# efuse.net
KiCad netlist of a schematic drawn in Altium Designer
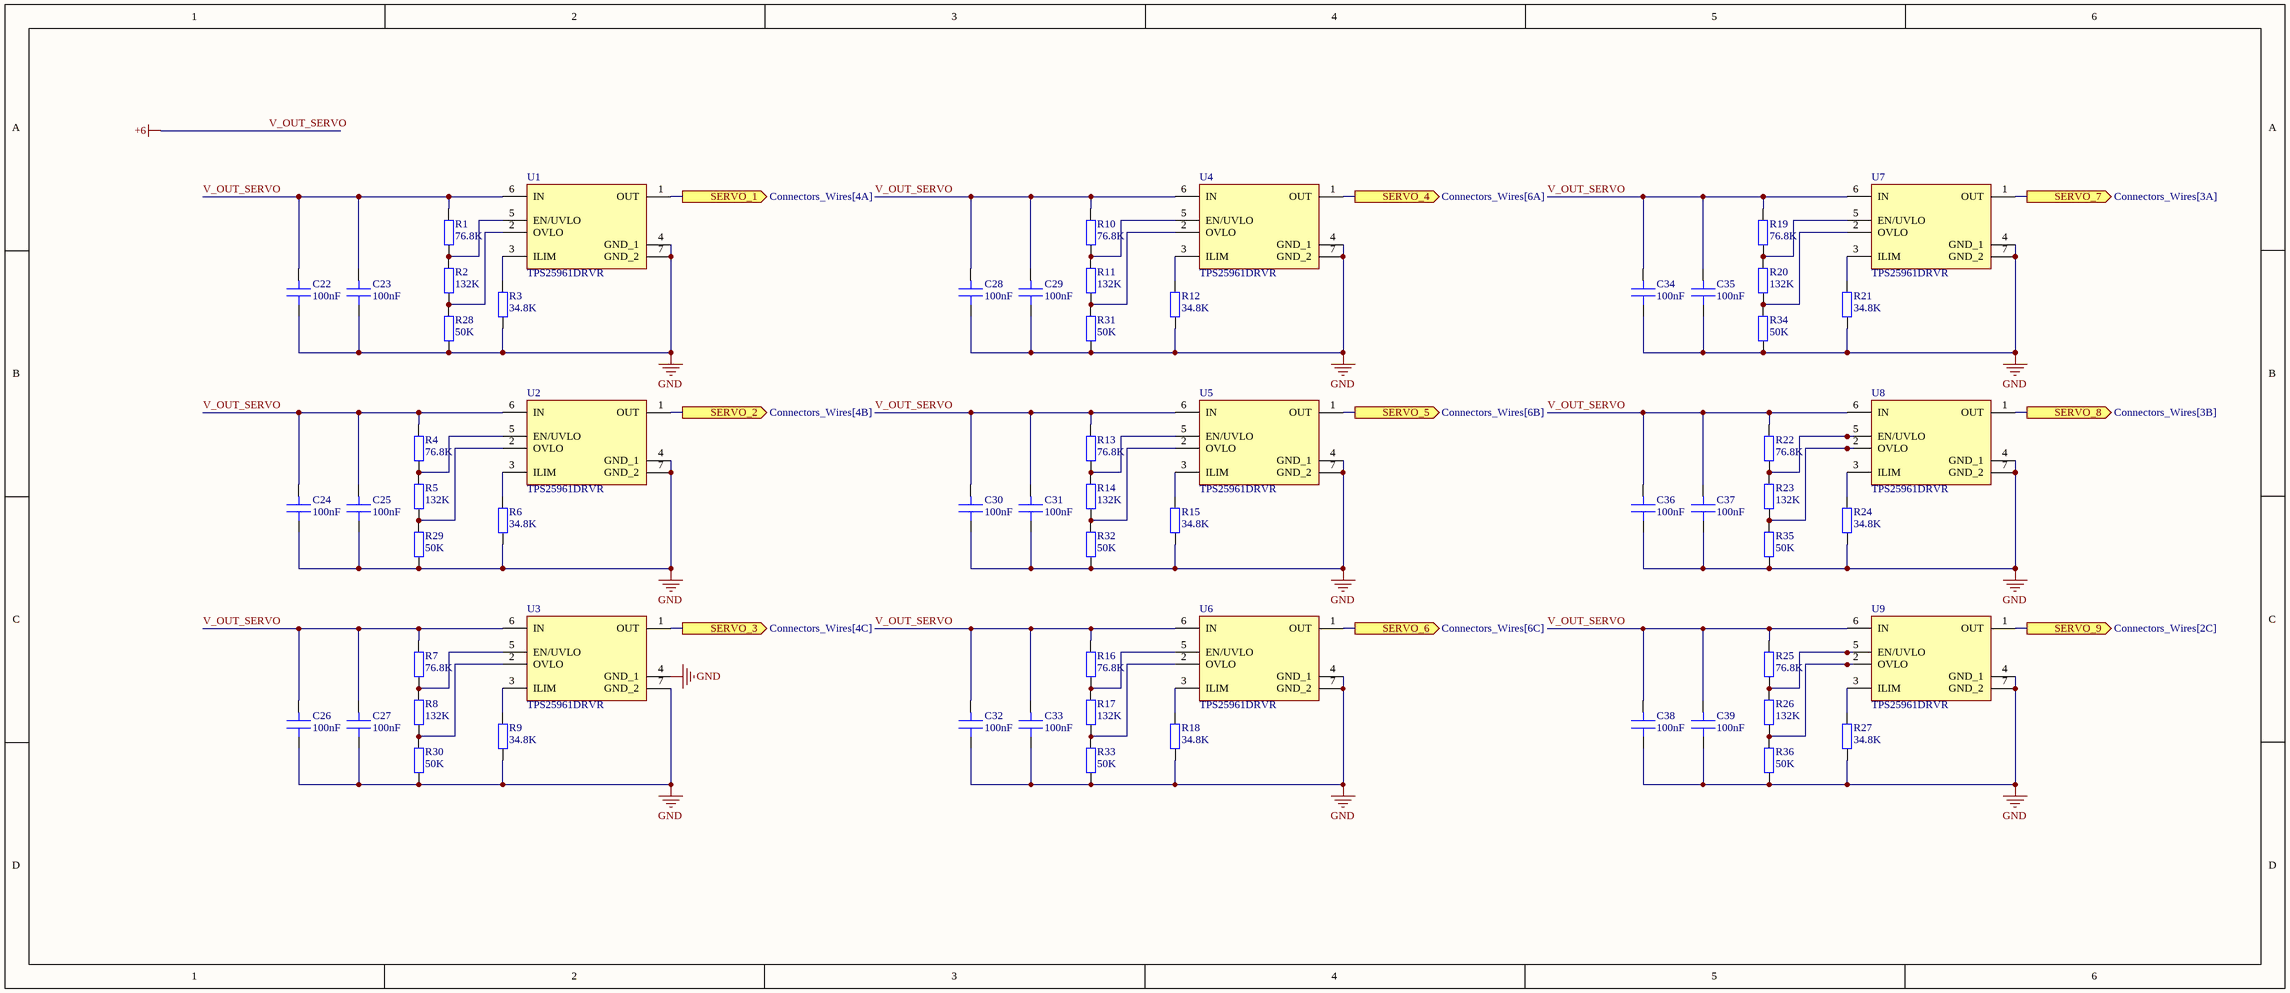
[diagram p0: efuse.SchDoc]

(export (version "E")
  (design (tool "Eeschema 10.0.6"))
  (components
    (comp (ref "C22")
      (value "100nF")
      (footprint "IPC C C0402 NO SILK")
      (description "Input capacitor")
      (libsource (lib "University of British Columbia") (part "Generic CAP 1210"))
    )
    (comp (ref "C23")
      (value "100nF")
      (footprint "IPC C C0402 NO SILK")
      (description "Input capacitor")
      (libsource (lib "University of British Columbia") (part "Generic CAP 1210"))
    )
    (comp (ref "C24")
      (value "100nF")
      (footprint "IPC C C0402 NO SILK")
      (description "Input capacitor")
      (libsource (lib "University of British Columbia") (part "Generic CAP 1210"))
    )
    (comp (ref "C25")
      (value "100nF")
      (footprint "IPC C C0402 NO SILK")
      (description "Input capacitor")
      (libsource (lib "University of British Columbia") (part "Generic CAP 1210"))
    )
    (comp (ref "C26")
      (value "100nF")
      (footprint "IPC C C0402 NO SILK")
      (description "Input capacitor")
      (libsource (lib "University of British Columbia") (part "Generic CAP 1210"))
    )
    (comp (ref "C27")
      (value "100nF")
      (footprint "IPC C C0402 NO SILK")
      (description "Input capacitor")
      (libsource (lib "University of British Columbia") (part "Generic CAP 1210"))
    )
    (comp (ref "C28")
      (value "100nF")
      (footprint "IPC C C0402 NO SILK")
      (description "Input capacitor")
      (libsource (lib "University of British Columbia") (part "Generic CAP 1210"))
    )
    (comp (ref "C29")
      (value "100nF")
      (footprint "IPC C C0402 NO SILK")
      (description "Input capacitor")
      (libsource (lib "University of British Columbia") (part "Generic CAP 1210"))
    )
    (comp (ref "C30")
      (value "100nF")
      (footprint "IPC C C0402 NO SILK")
      (description "Input capacitor")
      (libsource (lib "University of British Columbia") (part "Generic CAP 1210"))
    )
    (comp (ref "C31")
      (value "100nF")
      (footprint "IPC C C0402 NO SILK")
      (description "Input capacitor")
      (libsource (lib "University of British Columbia") (part "Generic CAP 1210"))
    )
    (comp (ref "C32")
      (value "100nF")
      (footprint "IPC C C0402 NO SILK")
      (description "Input capacitor")
      (libsource (lib "University of British Columbia") (part "Generic CAP 1210"))
    )
    (comp (ref "C33")
      (value "100nF")
      (footprint "IPC C C0402 NO SILK")
      (description "Input capacitor")
      (libsource (lib "University of British Columbia") (part "Generic CAP 1210"))
    )
    (comp (ref "C34")
      (value "100nF")
      (footprint "IPC C C0402 NO SILK")
      (description "Input capacitor")
      (libsource (lib "University of British Columbia") (part "Generic CAP 1210"))
    )
    (comp (ref "C35")
      (value "100nF")
      (footprint "IPC C C0402 NO SILK")
      (description "Input capacitor")
      (libsource (lib "University of British Columbia") (part "Generic CAP 1210"))
    )
    (comp (ref "C36")
      (value "100nF")
      (footprint "IPC C C0402 NO SILK")
      (description "Input capacitor")
      (libsource (lib "University of British Columbia") (part "Generic CAP 1210"))
    )
    (comp (ref "C37")
      (value "100nF")
      (footprint "IPC C C0402 NO SILK")
      (description "Input capacitor")
      (libsource (lib "University of British Columbia") (part "Generic CAP 1210"))
    )
    (comp (ref "C38")
      (value "100nF")
      (footprint "IPC C C0402 NO SILK")
      (description "Input capacitor")
      (libsource (lib "University of British Columbia") (part "Generic CAP 1210"))
    )
    (comp (ref "C39")
      (value "100nF")
      (footprint "IPC C C0402 NO SILK")
      (description "Input capacitor")
      (libsource (lib "University of British Columbia") (part "Generic CAP 1210"))
    )
    (comp (ref "R1")
      (value "76.8K")
      (footprint "IPC C R0402 NO SILK")
      (description "Generic RES 0402")
      (libsource (lib "University of British Columbia") (part "Generic RES 0603"))
    )
    (comp (ref "R2")
      (value "132K")
      (footprint "IPC C R0402 NO SILK")
      (description "Generic RES 0402")
      (libsource (lib "University of British Columbia") (part "Generic RES 0603"))
    )
    (comp (ref "R3")
      (value "34.8K")
      (footprint "IPC C R0402 NO SILK")
      (description "Generic RES 0402")
      (libsource (lib "University of British Columbia") (part "Generic RES 0603"))
    )
    (comp (ref "R4")
      (value "76.8K")
      (footprint "IPC C R0402 NO SILK")
      (description "Generic RES 0402")
      (libsource (lib "University of British Columbia") (part "Generic RES 0603"))
    )
    (comp (ref "R5")
      (value "132K")
      (footprint "IPC C R0402 NO SILK")
      (description "Generic RES 0402")
      (libsource (lib "University of British Columbia") (part "Generic RES 0603"))
    )
    (comp (ref "R6")
      (value "34.8K")
      (footprint "IPC C R0402 NO SILK")
      (description "Generic RES 0402")
      (libsource (lib "University of British Columbia") (part "Generic RES 0603"))
    )
    (comp (ref "R7")
      (value "76.8K")
      (footprint "IPC C R0402 NO SILK")
      (description "Generic RES 0402")
      (libsource (lib "University of British Columbia") (part "Generic RES 0603"))
    )
    (comp (ref "R8")
      (value "132K")
      (footprint "IPC C R0402 NO SILK")
      (description "Generic RES 0402")
      (libsource (lib "University of British Columbia") (part "Generic RES 0603"))
    )
    (comp (ref "R9")
      (value "34.8K")
      (footprint "IPC C R0402 NO SILK")
      (description "Generic RES 0402")
      (libsource (lib "University of British Columbia") (part "Generic RES 0603"))
    )
    (comp (ref "R10")
      (value "76.8K")
      (footprint "IPC C R0402 NO SILK")
      (description "Generic RES 0402")
      (libsource (lib "University of British Columbia") (part "Generic RES 0603"))
    )
    (comp (ref "R11")
      (value "132K")
      (footprint "IPC C R0402 NO SILK")
      (description "Generic RES 0402")
      (libsource (lib "University of British Columbia") (part "Generic RES 0603"))
    )
    (comp (ref "R12")
      (value "34.8K")
      (footprint "IPC C R0402 NO SILK")
      (description "Generic RES 0402")
      (libsource (lib "University of British Columbia") (part "Generic RES 0603"))
    )
    (comp (ref "R13")
      (value "76.8K")
      (footprint "IPC C R0402 NO SILK")
      (description "Generic RES 0402")
      (libsource (lib "University of British Columbia") (part "Generic RES 0603"))
    )
    (comp (ref "R14")
      (value "132K")
      (footprint "IPC C R0402 NO SILK")
      (description "Generic RES 0402")
      (libsource (lib "University of British Columbia") (part "Generic RES 0603"))
    )
    (comp (ref "R15")
      (value "34.8K")
      (footprint "IPC C R0402 NO SILK")
      (description "Generic RES 0402")
      (libsource (lib "University of British Columbia") (part "Generic RES 0603"))
    )
    (comp (ref "R16")
      (value "76.8K")
      (footprint "IPC C R0402 NO SILK")
      (description "Generic RES 0402")
      (libsource (lib "University of British Columbia") (part "Generic RES 0603"))
    )
    (comp (ref "R17")
      (value "132K")
      (footprint "IPC C R0402 NO SILK")
      (description "Generic RES 0402")
      (libsource (lib "University of British Columbia") (part "Generic RES 0603"))
    )
    (comp (ref "R18")
      (value "34.8K")
      (footprint "IPC C R0402 NO SILK")
      (description "Generic RES 0402")
      (libsource (lib "University of British Columbia") (part "Generic RES 0603"))
    )
    (comp (ref "R19")
      (value "76.8K")
      (footprint "IPC C R0402 NO SILK")
      (description "Generic RES 0402")
      (libsource (lib "University of British Columbia") (part "Generic RES 0603"))
    )
    (comp (ref "R20")
      (value "132K")
      (footprint "IPC C R0402 NO SILK")
      (description "Generic RES 0402")
      (libsource (lib "University of British Columbia") (part "Generic RES 0603"))
    )
    (comp (ref "R21")
      (value "34.8K")
      (footprint "IPC C R0402 NO SILK")
      (description "Generic RES 0402")
      (libsource (lib "University of British Columbia") (part "Generic RES 0603"))
    )
    (comp (ref "R22")
      (value "76.8K")
      (footprint "IPC C R0402 NO SILK")
      (description "Generic RES 0402")
      (libsource (lib "University of British Columbia") (part "Generic RES 0603"))
    )
    (comp (ref "R23")
      (value "132K")
      (footprint "IPC C R0402 NO SILK")
      (description "Generic RES 0402")
      (libsource (lib "University of British Columbia") (part "Generic RES 0603"))
    )
    (comp (ref "R24")
      (value "34.8K")
      (footprint "IPC C R0402 NO SILK")
      (description "Generic RES 0402")
      (libsource (lib "University of British Columbia") (part "Generic RES 0603"))
    )
    (comp (ref "R25")
      (value "76.8K")
      (footprint "IPC C R0402 NO SILK")
      (description "Generic RES 0402")
      (libsource (lib "University of British Columbia") (part "Generic RES 0603"))
    )
    (comp (ref "R26")
      (value "132K")
      (footprint "IPC C R0402 NO SILK")
      (description "Generic RES 0402")
      (libsource (lib "University of British Columbia") (part "Generic RES 0603"))
    )
    (comp (ref "R27")
      (value "34.8K")
      (footprint "IPC C R0402 NO SILK")
      (description "Generic RES 0402")
      (libsource (lib "University of British Columbia") (part "Generic RES 0603"))
    )
    (comp (ref "R28")
      (value "50K")
      (footprint "IPC C R0402 NO SILK")
      (description "Generic RES 0402")
      (libsource (lib "University of British Columbia") (part "Generic RES 0603"))
    )
    (comp (ref "R29")
      (value "50K")
      (footprint "IPC C R0402 NO SILK")
      (description "Generic RES 0402")
      (libsource (lib "University of British Columbia") (part "Generic RES 0603"))
    )
    (comp (ref "R30")
      (value "50K")
      (footprint "IPC C R0402 NO SILK")
      (description "Generic RES 0402")
      (libsource (lib "University of British Columbia") (part "Generic RES 0603"))
    )
    (comp (ref "R31")
      (value "50K")
      (footprint "IPC C R0402 NO SILK")
      (description "Generic RES 0402")
      (libsource (lib "University of British Columbia") (part "Generic RES 0603"))
    )
    (comp (ref "R32")
      (value "50K")
      (footprint "IPC C R0402 NO SILK")
      (description "Generic RES 0402")
      (libsource (lib "University of British Columbia") (part "Generic RES 0603"))
    )
    (comp (ref "R33")
      (value "50K")
      (footprint "IPC C R0402 NO SILK")
      (description "Generic RES 0402")
      (libsource (lib "University of British Columbia") (part "Generic RES 0603"))
    )
    (comp (ref "R34")
      (value "50K")
      (footprint "IPC C R0402 NO SILK")
      (description "Generic RES 0402")
      (libsource (lib "University of British Columbia") (part "Generic RES 0603"))
    )
    (comp (ref "R35")
      (value "50K")
      (footprint "IPC C R0402 NO SILK")
      (description "Generic RES 0402")
      (libsource (lib "University of British Columbia") (part "Generic RES 0603"))
    )
    (comp (ref "R36")
      (value "50K")
      (footprint "IPC C R0402 NO SILK")
      (description "Generic RES 0402")
      (libsource (lib "University of British Columbia") (part "Generic RES 0603"))
    )
    (comp (ref "U1")
      (value "TPS25961DRVR")
      (footprint "TPS25961DRVR-Footprint-1")
      (description "2.7-V TO 19-V 100-M EFUSE WITH O Hot Swap Controller 1 Channel General Purpose 6-WSON (2x2)")
      (libsource (lib "University of British Columbia") (part "TPS25961DRVR-Symbol-1"))
    )
    (comp (ref "U2")
      (value "TPS25961DRVR")
      (footprint "TPS25961DRVR-Footprint-1")
      (description "2.7-V TO 19-V 100-M EFUSE WITH O Hot Swap Controller 1 Channel General Purpose 6-WSON (2x2)")
      (libsource (lib "University of British Columbia") (part "TPS25961DRVR-Symbol-1"))
    )
    (comp (ref "U3")
      (value "TPS25961DRVR")
      (footprint "TPS25961DRVR-Footprint-1")
      (description "2.7-V TO 19-V 100-M EFUSE WITH O Hot Swap Controller 1 Channel General Purpose 6-WSON (2x2)")
      (libsource (lib "University of British Columbia") (part "TPS25961DRVR-Symbol-1"))
    )
    (comp (ref "U4")
      (value "TPS25961DRVR")
      (footprint "TPS25961DRVR-Footprint-1")
      (description "2.7-V TO 19-V 100-M EFUSE WITH O Hot Swap Controller 1 Channel General Purpose 6-WSON (2x2)")
      (libsource (lib "University of British Columbia") (part "TPS25961DRVR-Symbol-1"))
    )
    (comp (ref "U5")
      (value "TPS25961DRVR")
      (footprint "TPS25961DRVR-Footprint-1")
      (description "2.7-V TO 19-V 100-M EFUSE WITH O Hot Swap Controller 1 Channel General Purpose 6-WSON (2x2)")
      (libsource (lib "University of British Columbia") (part "TPS25961DRVR-Symbol-1"))
    )
    (comp (ref "U6")
      (value "TPS25961DRVR")
      (footprint "TPS25961DRVR-Footprint-1")
      (description "2.7-V TO 19-V 100-M EFUSE WITH O Hot Swap Controller 1 Channel General Purpose 6-WSON (2x2)")
      (libsource (lib "University of British Columbia") (part "TPS25961DRVR-Symbol-1"))
    )
    (comp (ref "U7")
      (value "TPS25961DRVR")
      (footprint "TPS25961DRVR-Footprint-1")
      (description "2.7-V TO 19-V 100-M EFUSE WITH O Hot Swap Controller 1 Channel General Purpose 6-WSON (2x2)")
      (libsource (lib "University of British Columbia") (part "TPS25961DRVR-Symbol-1"))
    )
    (comp (ref "U8")
      (value "TPS25961DRVR")
      (footprint "TPS25961DRVR-Footprint-1")
      (description "2.7-V TO 19-V 100-M EFUSE WITH O Hot Swap Controller 1 Channel General Purpose 6-WSON (2x2)")
      (libsource (lib "University of British Columbia") (part "TPS25961DRVR-Symbol-1"))
    )
    (comp (ref "U9")
      (value "TPS25961DRVR")
      (footprint "TPS25961DRVR-Footprint-1")
      (description "2.7-V TO 19-V 100-M EFUSE WITH O Hot Swap Controller 1 Channel General Purpose 6-WSON (2x2)")
      (libsource (lib "University of British Columbia") (part "TPS25961DRVR-Symbol-1"))
    )
  )
  (nets
    (net (code "1") (name "+6") (class "Default")
      (node (ref "C22") (pin "1") (pinfunction "1_1") (pintype "passive"))
      (node (ref "C23") (pin "1") (pinfunction "1_1") (pintype "passive"))
      (node (ref "C24") (pin "1") (pinfunction "1_1") (pintype "passive"))
      (node (ref "C25") (pin "1") (pinfunction "1_1") (pintype "passive"))
      (node (ref "C26") (pin "1") (pinfunction "1_1") (pintype "passive"))
      (node (ref "C27") (pin "1") (pinfunction "1_1") (pintype "passive"))
      (node (ref "C28") (pin "1") (pinfunction "1_1") (pintype "passive"))
      (node (ref "C29") (pin "1") (pinfunction "1_1") (pintype "passive"))
      (node (ref "C30") (pin "1") (pinfunction "1_1") (pintype "passive"))
      (node (ref "C31") (pin "1") (pinfunction "1_1") (pintype "passive"))
      (node (ref "C32") (pin "1") (pinfunction "1_1") (pintype "passive"))
      (node (ref "C33") (pin "1") (pinfunction "1_1") (pintype "passive"))
      (node (ref "C34") (pin "1") (pinfunction "1_1") (pintype "passive"))
      (node (ref "C35") (pin "1") (pinfunction "1_1") (pintype "passive"))
      (node (ref "C36") (pin "1") (pinfunction "1_1") (pintype "passive"))
      (node (ref "C37") (pin "1") (pinfunction "1_1") (pintype "passive"))
      (node (ref "C38") (pin "1") (pinfunction "1_1") (pintype "passive"))
      (node (ref "C39") (pin "1") (pinfunction "1_1") (pintype "passive"))
      (node (ref "R1") (pin "2") (pinfunction "2_2") (pintype "passive"))
      (node (ref "R10") (pin "2") (pinfunction "2_2") (pintype "passive"))
      (node (ref "R13") (pin "2") (pinfunction "2_2") (pintype "passive"))
      (node (ref "R16") (pin "2") (pinfunction "2_2") (pintype "passive"))
      (node (ref "R19") (pin "2") (pinfunction "2_2") (pintype "passive"))
      (node (ref "R22") (pin "2") (pinfunction "2_2") (pintype "passive"))
      (node (ref "R25") (pin "2") (pinfunction "2_2") (pintype "passive"))
      (node (ref "R4") (pin "2") (pinfunction "2_2") (pintype "passive"))
      (node (ref "R7") (pin "2") (pinfunction "2_2") (pintype "passive"))
      (node (ref "U1") (pin "6") (pinfunction "IN_6") (pintype "power_in"))
      (node (ref "U2") (pin "6") (pinfunction "IN_6") (pintype "power_in"))
      (node (ref "U3") (pin "6") (pinfunction "IN_6") (pintype "power_in"))
      (node (ref "U4") (pin "6") (pinfunction "IN_6") (pintype "power_in"))
      (node (ref "U5") (pin "6") (pinfunction "IN_6") (pintype "power_in"))
      (node (ref "U6") (pin "6") (pinfunction "IN_6") (pintype "power_in"))
      (node (ref "U7") (pin "6") (pinfunction "IN_6") (pintype "power_in"))
      (node (ref "U8") (pin "6") (pinfunction "IN_6") (pintype "power_in"))
      (node (ref "U9") (pin "6") (pinfunction "IN_6") (pintype "power_in"))
    )
    (net (code "2") (name "/SERVO_1") (class "Default")
      (node (ref "U1") (pin "1") (pinfunction "OUT_1") (pintype "passive"))
    )
    (net (code "3") (name "/SERVO_2") (class "Default")
      (node (ref "U2") (pin "1") (pinfunction "OUT_1") (pintype "passive"))
    )
    (net (code "4") (name "/SERVO_3") (class "Default")
      (node (ref "U3") (pin "1") (pinfunction "OUT_1") (pintype "passive"))
    )
    (net (code "5") (name "/SERVO_4") (class "Default")
      (node (ref "U4") (pin "1") (pinfunction "OUT_1") (pintype "passive"))
    )
    (net (code "6") (name "/SERVO_5") (class "Default")
      (node (ref "U5") (pin "1") (pinfunction "OUT_1") (pintype "passive"))
    )
    (net (code "7") (name "/SERVO_6") (class "Default")
      (node (ref "U6") (pin "1") (pinfunction "OUT_1") (pintype "passive"))
    )
    (net (code "8") (name "/SERVO_7") (class "Default")
      (node (ref "U7") (pin "1") (pinfunction "OUT_1") (pintype "passive"))
    )
    (net (code "9") (name "/SERVO_8") (class "Default")
      (node (ref "U8") (pin "1") (pinfunction "OUT_1") (pintype "passive"))
    )
    (net (code "10") (name "/SERVO_9") (class "Default")
      (node (ref "U9") (pin "1") (pinfunction "OUT_1") (pintype "passive"))
    )
    (net (code "11") (name "GND") (class "Default")
      (node (ref "C22") (pin "2") (pinfunction "2_2") (pintype "passive"))
      (node (ref "C23") (pin "2") (pinfunction "2_2") (pintype "passive"))
      (node (ref "C24") (pin "2") (pinfunction "2_2") (pintype "passive"))
      (node (ref "C25") (pin "2") (pinfunction "2_2") (pintype "passive"))
      (node (ref "C26") (pin "2") (pinfunction "2_2") (pintype "passive"))
      (node (ref "C27") (pin "2") (pinfunction "2_2") (pintype "passive"))
      (node (ref "C28") (pin "2") (pinfunction "2_2") (pintype "passive"))
      (node (ref "C29") (pin "2") (pinfunction "2_2") (pintype "passive"))
      (node (ref "C30") (pin "2") (pinfunction "2_2") (pintype "passive"))
      (node (ref "C31") (pin "2") (pinfunction "2_2") (pintype "passive"))
      (node (ref "C32") (pin "2") (pinfunction "2_2") (pintype "passive"))
      (node (ref "C33") (pin "2") (pinfunction "2_2") (pintype "passive"))
      (node (ref "C34") (pin "2") (pinfunction "2_2") (pintype "passive"))
      (node (ref "C35") (pin "2") (pinfunction "2_2") (pintype "passive"))
      (node (ref "C36") (pin "2") (pinfunction "2_2") (pintype "passive"))
      (node (ref "C37") (pin "2") (pinfunction "2_2") (pintype "passive"))
      (node (ref "C38") (pin "2") (pinfunction "2_2") (pintype "passive"))
      (node (ref "C39") (pin "2") (pinfunction "2_2") (pintype "passive"))
      (node (ref "R12") (pin "1") (pinfunction "1_1") (pintype "passive"))
      (node (ref "R15") (pin "1") (pinfunction "1_1") (pintype "passive"))
      (node (ref "R18") (pin "1") (pinfunction "1_1") (pintype "passive"))
      (node (ref "R21") (pin "1") (pinfunction "1_1") (pintype "passive"))
      (node (ref "R24") (pin "1") (pinfunction "1_1") (pintype "passive"))
      (node (ref "R27") (pin "1") (pinfunction "1_1") (pintype "passive"))
      (node (ref "R28") (pin "1") (pinfunction "1_1") (pintype "passive"))
      (node (ref "R29") (pin "1") (pinfunction "1_1") (pintype "passive"))
      (node (ref "R3") (pin "1") (pinfunction "1_1") (pintype "passive"))
      (node (ref "R30") (pin "1") (pinfunction "1_1") (pintype "passive"))
      (node (ref "R31") (pin "1") (pinfunction "1_1") (pintype "passive"))
      (node (ref "R32") (pin "1") (pinfunction "1_1") (pintype "passive"))
      (node (ref "R33") (pin "1") (pinfunction "1_1") (pintype "passive"))
      (node (ref "R34") (pin "1") (pinfunction "1_1") (pintype "passive"))
      (node (ref "R35") (pin "1") (pinfunction "1_1") (pintype "passive"))
      (node (ref "R36") (pin "1") (pinfunction "1_1") (pintype "passive"))
      (node (ref "R6") (pin "1") (pinfunction "1_1") (pintype "passive"))
      (node (ref "R9") (pin "1") (pinfunction "1_1") (pintype "passive"))
      (node (ref "U1") (pin "4") (pinfunction "GND_1_4") (pintype "passive"))
      (node (ref "U1") (pin "7") (pinfunction "GND_2_7") (pintype "passive"))
      (node (ref "U2") (pin "4") (pinfunction "GND_1_4") (pintype "passive"))
      (node (ref "U2") (pin "7") (pinfunction "GND_2_7") (pintype "passive"))
      (node (ref "U3") (pin "4") (pinfunction "GND_1_4") (pintype "passive"))
      (node (ref "U3") (pin "7") (pinfunction "GND_2_7") (pintype "passive"))
      (node (ref "U4") (pin "4") (pinfunction "GND_1_4") (pintype "passive"))
      (node (ref "U4") (pin "7") (pinfunction "GND_2_7") (pintype "passive"))
      (node (ref "U5") (pin "4") (pinfunction "GND_1_4") (pintype "passive"))
      (node (ref "U5") (pin "7") (pinfunction "GND_2_7") (pintype "passive"))
      (node (ref "U6") (pin "4") (pinfunction "GND_1_4") (pintype "passive"))
      (node (ref "U6") (pin "7") (pinfunction "GND_2_7") (pintype "passive"))
      (node (ref "U7") (pin "4") (pinfunction "GND_1_4") (pintype "passive"))
      (node (ref "U7") (pin "7") (pinfunction "GND_2_7") (pintype "passive"))
      (node (ref "U8") (pin "4") (pinfunction "GND_1_4") (pintype "passive"))
      (node (ref "U8") (pin "7") (pinfunction "GND_2_7") (pintype "passive"))
      (node (ref "U9") (pin "4") (pinfunction "GND_1_4") (pintype "passive"))
      (node (ref "U9") (pin "7") (pinfunction "GND_2_7") (pintype "passive"))
    )
    (net (code "12") (name "Net-(U1-EN{slash}UVLO)") (class "Default")
      (node (ref "R1") (pin "1") (pinfunction "1_1") (pintype "passive"))
      (node (ref "R2") (pin "2") (pinfunction "2_2") (pintype "passive"))
      (node (ref "U1") (pin "5") (pinfunction "EN/UVLO_5") (pintype "passive"))
    )
    (net (code "13") (name "Net-(U1-ILIM)") (class "Default")
      (node (ref "R3") (pin "2") (pinfunction "2_2") (pintype "passive"))
      (node (ref "U1") (pin "3") (pinfunction "ILIM_3") (pintype "passive"))
    )
    (net (code "14") (name "Net-(U1-OVLO)") (class "Default")
      (node (ref "R2") (pin "1") (pinfunction "1_1") (pintype "passive"))
      (node (ref "R28") (pin "2") (pinfunction "2_2") (pintype "passive"))
      (node (ref "U1") (pin "2") (pinfunction "OVLO_2") (pintype "passive"))
    )
    (net (code "15") (name "Net-(U2-EN{slash}UVLO)") (class "Default")
      (node (ref "R4") (pin "1") (pinfunction "1_1") (pintype "passive"))
      (node (ref "R5") (pin "2") (pinfunction "2_2") (pintype "passive"))
      (node (ref "U2") (pin "5") (pinfunction "EN/UVLO_5") (pintype "passive"))
    )
    (net (code "16") (name "Net-(U2-ILIM)") (class "Default")
      (node (ref "R6") (pin "2") (pinfunction "2_2") (pintype "passive"))
      (node (ref "U2") (pin "3") (pinfunction "ILIM_3") (pintype "passive"))
    )
    (net (code "17") (name "Net-(U2-OVLO)") (class "Default")
      (node (ref "R29") (pin "2") (pinfunction "2_2") (pintype "passive"))
      (node (ref "R5") (pin "1") (pinfunction "1_1") (pintype "passive"))
      (node (ref "U2") (pin "2") (pinfunction "OVLO_2") (pintype "passive"))
    )
    (net (code "18") (name "Net-(U3-EN{slash}UVLO)") (class "Default")
      (node (ref "R7") (pin "1") (pinfunction "1_1") (pintype "passive"))
      (node (ref "R8") (pin "2") (pinfunction "2_2") (pintype "passive"))
      (node (ref "U3") (pin "5") (pinfunction "EN/UVLO_5") (pintype "passive"))
    )
    (net (code "19") (name "Net-(U3-ILIM)") (class "Default")
      (node (ref "R9") (pin "2") (pinfunction "2_2") (pintype "passive"))
      (node (ref "U3") (pin "3") (pinfunction "ILIM_3") (pintype "passive"))
    )
    (net (code "20") (name "Net-(U3-OVLO)") (class "Default")
      (node (ref "R30") (pin "2") (pinfunction "2_2") (pintype "passive"))
      (node (ref "R8") (pin "1") (pinfunction "1_1") (pintype "passive"))
      (node (ref "U3") (pin "2") (pinfunction "OVLO_2") (pintype "passive"))
    )
    (net (code "21") (name "Net-(U4-EN{slash}UVLO)") (class "Default")
      (node (ref "R10") (pin "1") (pinfunction "1_1") (pintype "passive"))
      (node (ref "R11") (pin "2") (pinfunction "2_2") (pintype "passive"))
      (node (ref "U4") (pin "5") (pinfunction "EN/UVLO_5") (pintype "passive"))
    )
    (net (code "22") (name "Net-(U4-ILIM)") (class "Default")
      (node (ref "R12") (pin "2") (pinfunction "2_2") (pintype "passive"))
      (node (ref "U4") (pin "3") (pinfunction "ILIM_3") (pintype "passive"))
    )
    (net (code "23") (name "Net-(U4-OVLO)") (class "Default")
      (node (ref "R11") (pin "1") (pinfunction "1_1") (pintype "passive"))
      (node (ref "R31") (pin "2") (pinfunction "2_2") (pintype "passive"))
      (node (ref "U4") (pin "2") (pinfunction "OVLO_2") (pintype "passive"))
    )
    (net (code "24") (name "Net-(U5-EN{slash}UVLO)") (class "Default")
      (node (ref "R13") (pin "1") (pinfunction "1_1") (pintype "passive"))
      (node (ref "R14") (pin "2") (pinfunction "2_2") (pintype "passive"))
      (node (ref "U5") (pin "5") (pinfunction "EN/UVLO_5") (pintype "passive"))
    )
    (net (code "25") (name "Net-(U5-ILIM)") (class "Default")
      (node (ref "R15") (pin "2") (pinfunction "2_2") (pintype "passive"))
      (node (ref "U5") (pin "3") (pinfunction "ILIM_3") (pintype "passive"))
    )
    (net (code "26") (name "Net-(U5-OVLO)") (class "Default")
      (node (ref "R14") (pin "1") (pinfunction "1_1") (pintype "passive"))
      (node (ref "R32") (pin "2") (pinfunction "2_2") (pintype "passive"))
      (node (ref "U5") (pin "2") (pinfunction "OVLO_2") (pintype "passive"))
    )
    (net (code "27") (name "Net-(U6-EN{slash}UVLO)") (class "Default")
      (node (ref "R16") (pin "1") (pinfunction "1_1") (pintype "passive"))
      (node (ref "R17") (pin "2") (pinfunction "2_2") (pintype "passive"))
      (node (ref "U6") (pin "5") (pinfunction "EN/UVLO_5") (pintype "passive"))
    )
    (net (code "28") (name "Net-(U6-ILIM)") (class "Default")
      (node (ref "R18") (pin "2") (pinfunction "2_2") (pintype "passive"))
      (node (ref "U6") (pin "3") (pinfunction "ILIM_3") (pintype "passive"))
    )
    (net (code "29") (name "Net-(U6-OVLO)") (class "Default")
      (node (ref "R17") (pin "1") (pinfunction "1_1") (pintype "passive"))
      (node (ref "R33") (pin "2") (pinfunction "2_2") (pintype "passive"))
      (node (ref "U6") (pin "2") (pinfunction "OVLO_2") (pintype "passive"))
    )
    (net (code "30") (name "Net-(U7-EN{slash}UVLO)") (class "Default")
      (node (ref "R19") (pin "1") (pinfunction "1_1") (pintype "passive"))
      (node (ref "R20") (pin "2") (pinfunction "2_2") (pintype "passive"))
      (node (ref "U7") (pin "5") (pinfunction "EN/UVLO_5") (pintype "passive"))
    )
    (net (code "31") (name "Net-(U7-ILIM)") (class "Default")
      (node (ref "R21") (pin "2") (pinfunction "2_2") (pintype "passive"))
      (node (ref "U7") (pin "3") (pinfunction "ILIM_3") (pintype "passive"))
    )
    (net (code "32") (name "Net-(U7-OVLO)") (class "Default")
      (node (ref "R20") (pin "1") (pinfunction "1_1") (pintype "passive"))
      (node (ref "R34") (pin "2") (pinfunction "2_2") (pintype "passive"))
      (node (ref "U7") (pin "2") (pinfunction "OVLO_2") (pintype "passive"))
    )
    (net (code "33") (name "Net-(U8-EN{slash}UVLO)") (class "Default")
      (node (ref "R22") (pin "1") (pinfunction "1_1") (pintype "passive"))
      (node (ref "R23") (pin "2") (pinfunction "2_2") (pintype "passive"))
      (node (ref "U8") (pin "5") (pinfunction "EN/UVLO_5") (pintype "passive"))
    )
    (net (code "34") (name "Net-(U8-ILIM)") (class "Default")
      (node (ref "R24") (pin "2") (pinfunction "2_2") (pintype "passive"))
      (node (ref "U8") (pin "3") (pinfunction "ILIM_3") (pintype "passive"))
    )
    (net (code "35") (name "Net-(U8-OVLO)") (class "Default")
      (node (ref "R23") (pin "1") (pinfunction "1_1") (pintype "passive"))
      (node (ref "R35") (pin "2") (pinfunction "2_2") (pintype "passive"))
      (node (ref "U8") (pin "2") (pinfunction "OVLO_2") (pintype "passive"))
    )
    (net (code "36") (name "Net-(U9-EN{slash}UVLO)") (class "Default")
      (node (ref "R25") (pin "1") (pinfunction "1_1") (pintype "passive"))
      (node (ref "R26") (pin "2") (pinfunction "2_2") (pintype "passive"))
      (node (ref "U9") (pin "5") (pinfunction "EN/UVLO_5") (pintype "passive"))
    )
    (net (code "37") (name "Net-(U9-ILIM)") (class "Default")
      (node (ref "R27") (pin "2") (pinfunction "2_2") (pintype "passive"))
      (node (ref "U9") (pin "3") (pinfunction "ILIM_3") (pintype "passive"))
    )
    (net (code "38") (name "Net-(U9-OVLO)") (class "Default")
      (node (ref "R26") (pin "1") (pinfunction "1_1") (pintype "passive"))
      (node (ref "R36") (pin "2") (pinfunction "2_2") (pintype "passive"))
      (node (ref "U9") (pin "2") (pinfunction "OVLO_2") (pintype "passive"))
    )
  )
)
